# Power.net
KiCad netlist of a schematic drawn in Altium Designer
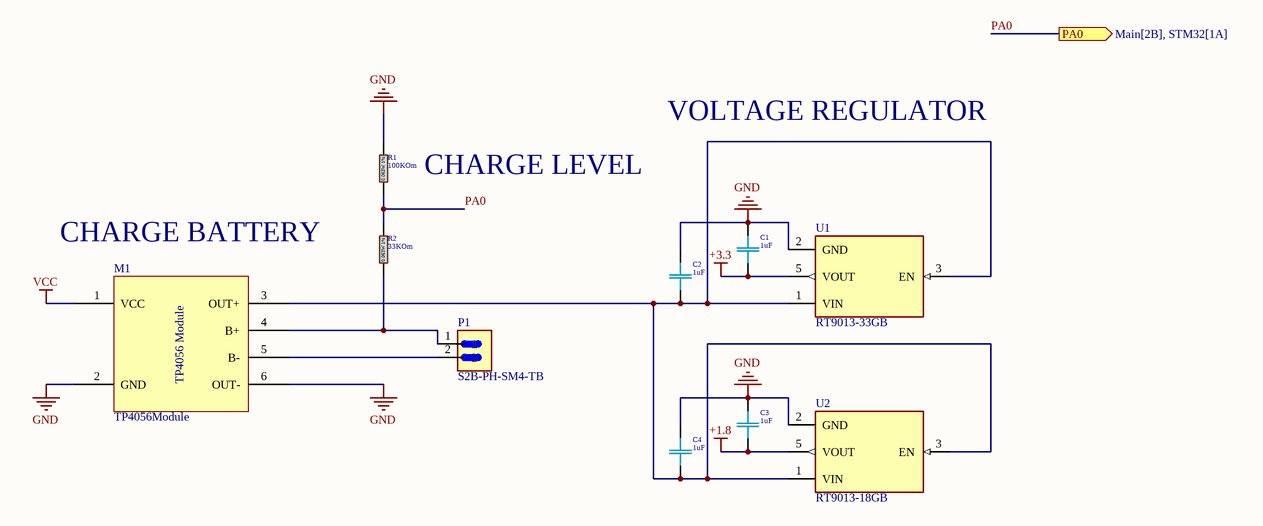
[diagram p0: Power.SchDoc]

(export (version "E")
  (design (tool "Eeschema 10.0.6"))
  (components
    (comp (ref "C1")
      (value "1uF")
      (footprint "C 0402(1005)x0.5")
      (description "SMD 0402     16V X5R 10%")
      (fields (field (name "MANUFACTURER") "Samsung") (field (name "PUBLISHER") "Hefest"))
      (libsource (lib "SMD Passive") (part "C 0402    16V X5R - 0*"))
    )
    (comp (ref "C2")
      (value "1uF")
      (footprint "C 0402(1005)x0.5")
      (description "SMD 0402     16V X5R 10%")
      (fields (field (name "MANUFACTURER") "Samsung") (field (name "PUBLISHER") "Hefest"))
      (libsource (lib "SMD Passive") (part "C 0402    16V X5R - 0*"))
    )
    (comp (ref "C3")
      (value "1uF")
      (footprint "C 0402(1005)x0.5")
      (description "SMD 0402     16V X5R 10%")
      (fields (field (name "MANUFACTURER") "Samsung") (field (name "PUBLISHER") "Hefest"))
      (libsource (lib "SMD Passive") (part "C 0402    16V X5R - 0*"))
    )
    (comp (ref "C4")
      (value "1uF")
      (footprint "C 0402(1005)x0.5")
      (description "SMD 0402     16V X5R 10%")
      (fields (field (name "MANUFACTURER") "Samsung") (field (name "PUBLISHER") "Hefest"))
      (libsource (lib "SMD Passive") (part "C 0402    16V X5R - 0*"))
    )
    (comp (ref "M1")
      (value "TP4056Module")
      (footprint "TP4056Module")
      (description "TP4056 Module for managing battery charging")
      (libsource (lib "Module TP4056") (part "TP4056Module"))
    )
    (comp (ref "P1")
      (value "S2B-PH-SM4-TB")
      (footprint "JST_S2B-PH-SM4-TB")
      (description "Connector Header Surface Mount, Right Angle 2 position 0.079 (2.00mm)")
      (fields (field (name "MF") "JST Sales"))
      (libsource (lib "S2B-PH-SM4-TB") (part "S2B-PH-SM4-TB"))
    )
    (comp (ref "R1")
      (value "100KOm")
      (footprint "R 0402(1005)-1%")
      (description "SMD 0402 0.063W 1%   50V")
      (fields
        (field (name "MANUFACTURER") "YAGEO")
        (field (name "POWER") "0.0625W")
        (field (name "PUBLISHER") "Hefest")
      )
      (libsource (lib "SMD Passive") (part "R 0402-1%"))
    )
    (comp (ref "R2")
      (value "33KOm")
      (footprint "R 0402(1005)-1%")
      (description "SMD 0402 0.063W 1%   50V")
      (fields
        (field (name "MANUFACTURER") "YAGEO")
        (field (name "POWER") "0.0625W")
        (field (name "PUBLISHER") "Hefest")
      )
      (libsource (lib "SMD Passive") (part "R 0402-1%"))
    )
    (comp (ref "U1")
      (value "RT9013-33GB")
      (footprint "SOT94P279X129-5N")
      (description "Linear Voltage Regulator IC 1 Output 500mA SOT-23-5")
      (fields (field (name "MF") "Richtek USA"))
      (libsource (lib "RT9013-33GB") (part "RT9013-33GB"))
    )
    (comp (ref "U2")
      (value "RT9013-18GB")
      (footprint "SOT94P279X129-5N")
      (description "Linear Voltage Regulator IC 1 Output 500mA SOT-23-5")
      (fields (field (name "MF") "Richtek USA") (field (name "MP") "RT9013-33GB"))
      (libsource (lib "RT9013-33GB") (part "RT9013-33GB"))
    )
  )
  (nets
    (net (code "1") (name "+1.8") (class "Default")
      (node (ref "C3") (pin "2") (pinfunction "2_2") (pintype "passive"))
      (node (ref "U2") (pin "5") (pinfunction "VOUT_5") (pintype "output"))
    )
    (net (code "2") (name "+3.3") (class "Default")
      (node (ref "C1") (pin "2") (pinfunction "2_2") (pintype "passive"))
      (node (ref "U1") (pin "5") (pinfunction "VOUT_5") (pintype "output"))
    )
    (net (code "3") (name "/PA0") (class "Default")
      (node (ref "R1") (pin "1") (pinfunction "1_1") (pintype "passive"))
      (node (ref "R2") (pin "2") (pinfunction "2_2") (pintype "passive"))
    )
    (net (code "4") (name "GND") (class "Default")
      (node (ref "C1") (pin "1") (pinfunction "1_1") (pintype "passive"))
      (node (ref "C2") (pin "1") (pinfunction "1_1") (pintype "passive"))
      (node (ref "C3") (pin "1") (pinfunction "1_1") (pintype "passive"))
      (node (ref "C4") (pin "1") (pinfunction "1_1") (pintype "passive"))
      (node (ref "M1") (pin "2") (pinfunction "GND_2") (pintype "passive"))
      (node (ref "M1") (pin "6") (pinfunction "OUT-_6") (pintype "passive"))
      (node (ref "R1") (pin "2") (pinfunction "2_2") (pintype "passive"))
      (node (ref "U1") (pin "2") (pinfunction "GND_2") (pintype "power_in"))
      (node (ref "U2") (pin "2") (pinfunction "GND_2") (pintype "power_in"))
    )
    (net (code "5") (name "Net-(M1-B+)") (class "Default")
      (node (ref "M1") (pin "4") (pinfunction "B+_4") (pintype "passive"))
      (node (ref "P1") (pin "1") (pinfunction "1_1") (pintype "passive"))
      (node (ref "R2") (pin "1") (pinfunction "1_1") (pintype "passive"))
    )
    (net (code "6") (name "Net-(M1-B-)") (class "Default")
      (node (ref "M1") (pin "5") (pinfunction "B-_5") (pintype "passive"))
      (node (ref "P1") (pin "2") (pinfunction "2_2") (pintype "passive"))
    )
    (net (code "7") (name "Net-(M1-OUT+)") (class "Default")
      (node (ref "C2") (pin "2") (pinfunction "2_2") (pintype "passive"))
      (node (ref "C4") (pin "2") (pinfunction "2_2") (pintype "passive"))
      (node (ref "M1") (pin "3") (pinfunction "OUT+_3") (pintype "passive"))
      (node (ref "U1") (pin "1") (pinfunction "VIN_1") (pintype "power_in"))
      (node (ref "U1") (pin "3") (pinfunction "EN_3") (pintype "input"))
      (node (ref "U2") (pin "1") (pinfunction "VIN_1") (pintype "power_in"))
      (node (ref "U2") (pin "3") (pinfunction "EN_3") (pintype "input"))
    )
    (net (code "8") (name "VCC") (class "Default")
      (node (ref "M1") (pin "1") (pinfunction "VCC_1") (pintype "passive"))
    )
  )
)
